# TAS5711.net
KiCad netlist of a schematic drawn in Altium Designer
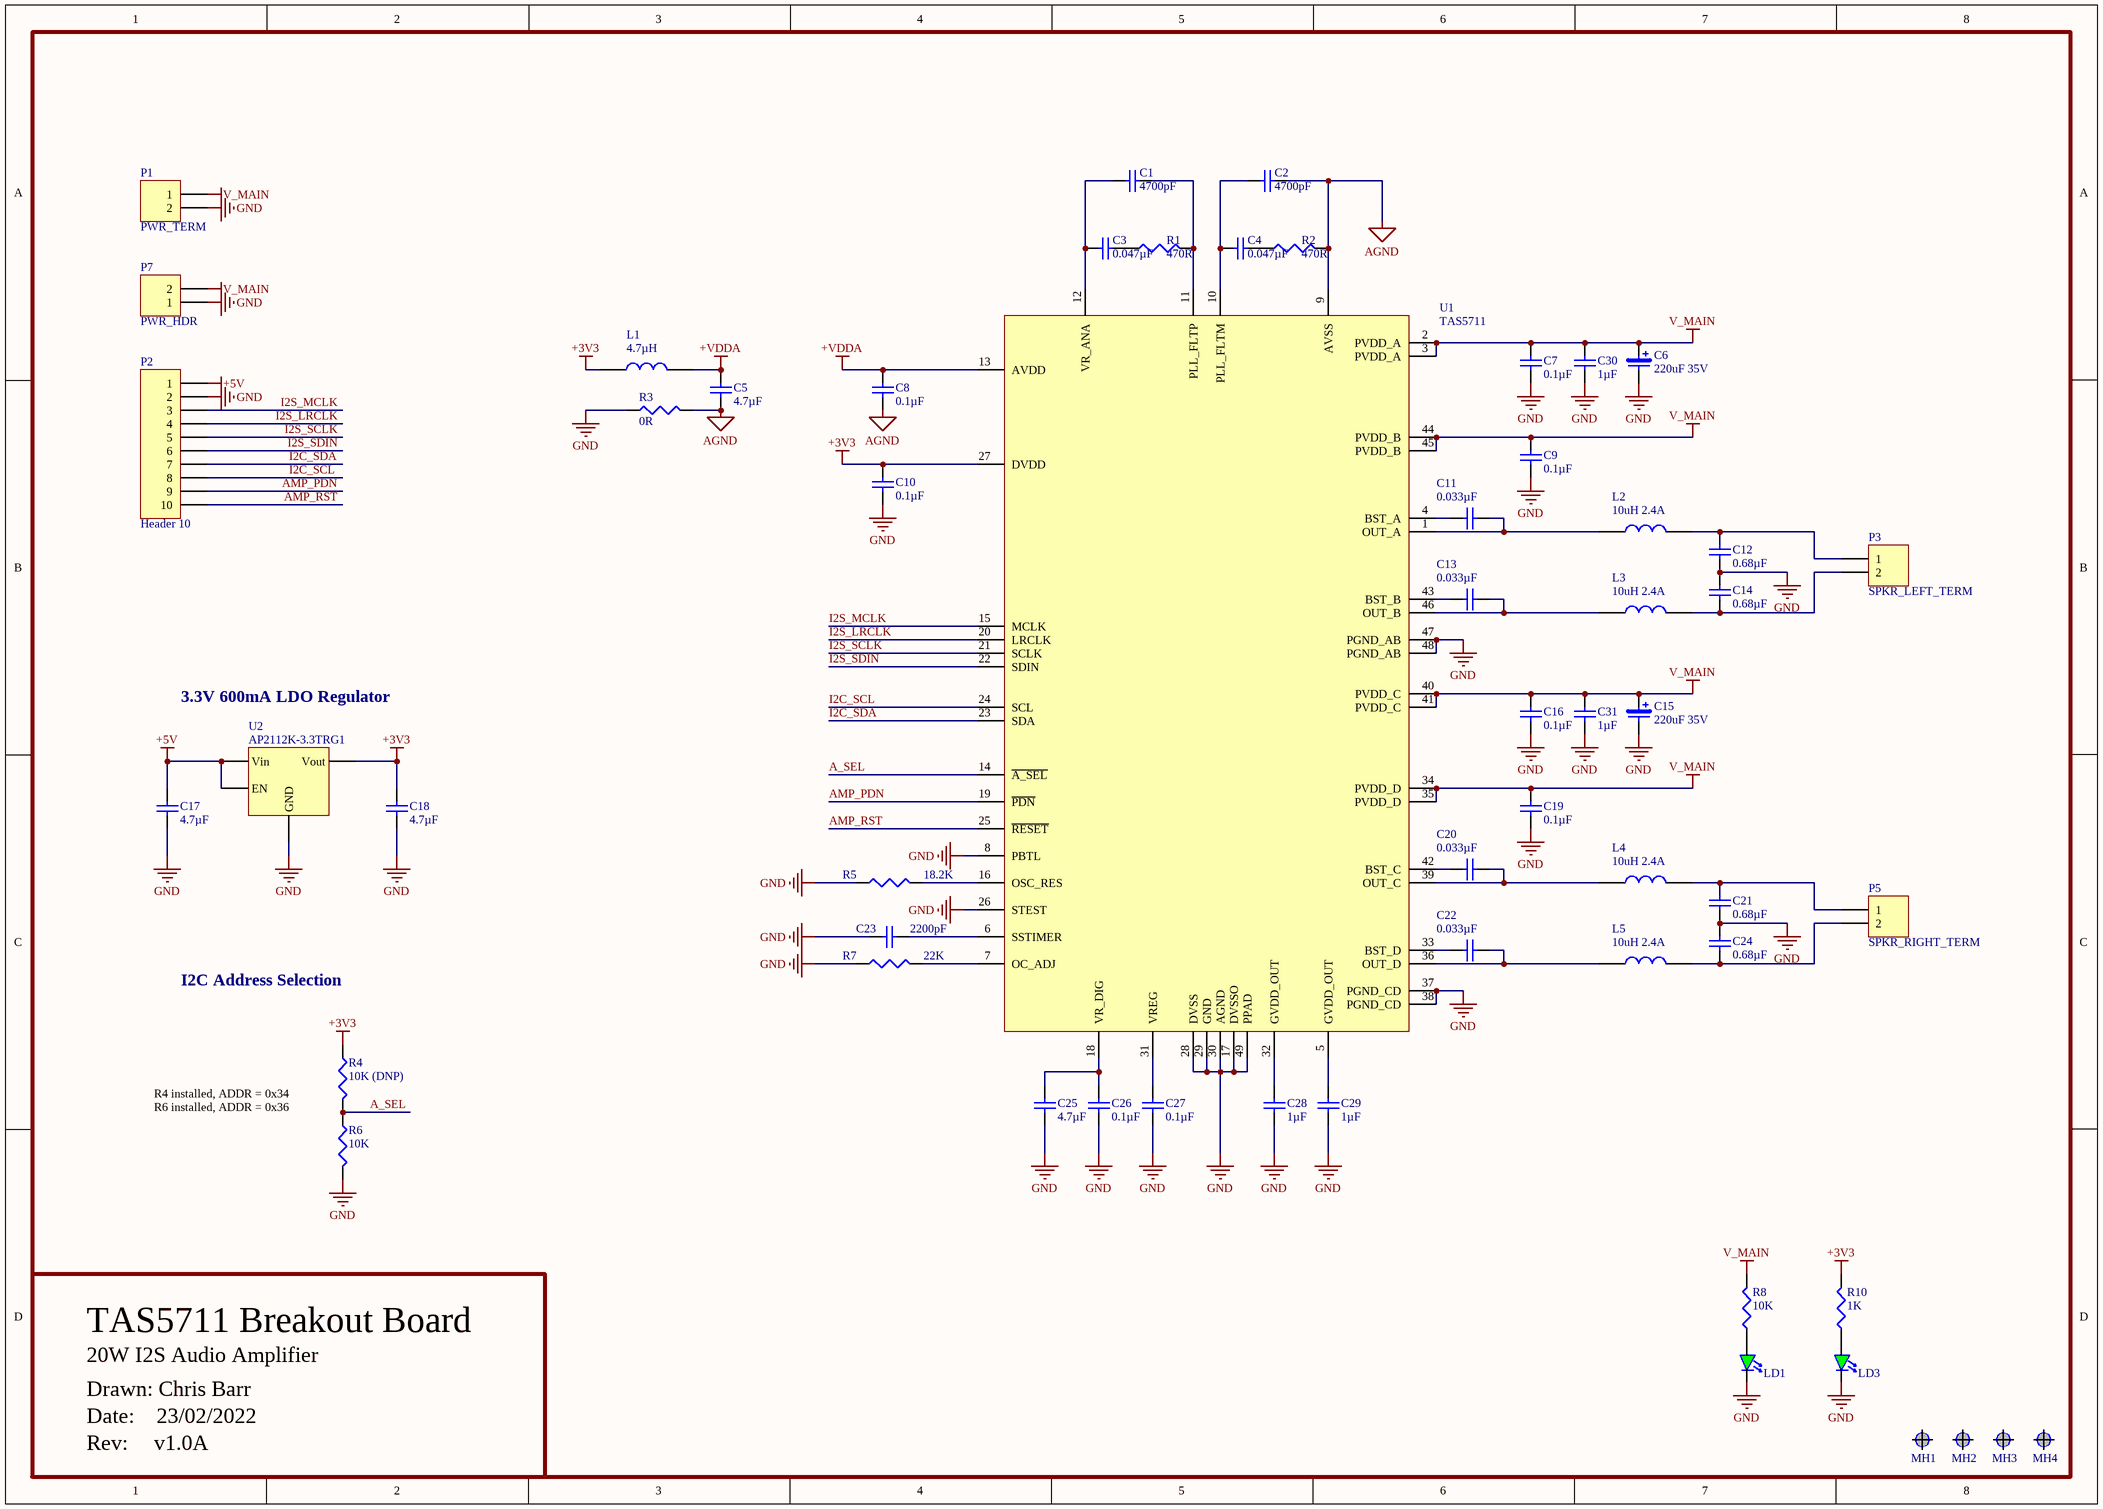
[diagram p0: TAS5711.SchDoc]

(export (version "E")
  (design (tool "Eeschema 10.0.6"))
  (components
    (comp (ref "C1")
      (value "4700pF")
      (footprint "CAPC1608X90N")
      (description "CAP CER 4700PF 50V X7R 0603")
      (fields (field (name "VOLTAGE") "50V") (field (name "TOLERANCE") "±10%"))
      (libsource (lib "Ceramic Cap DBLIB") (part "Capacitor"))
    )
    (comp (ref "C2")
      (value "4700pF")
      (footprint "CAPC1608X90N")
      (description "CAP CER 4700PF 50V X7R 0603")
      (fields (field (name "VOLTAGE") "50V") (field (name "TOLERANCE") "±10%"))
      (libsource (lib "Ceramic Cap DBLIB") (part "Capacitor"))
    )
    (comp (ref "C3")
      (value "0.047µF")
      (footprint "CAPC1608X90N")
      (description "CAP CER 0.047UF 25V X5R 0603")
      (fields (field (name "VOLTAGE") "25V") (field (name "TOLERANCE") "±10%"))
      (libsource (lib "Ceramic Cap DBLIB") (part "Capacitor"))
    )
    (comp (ref "C4")
      (value "0.047µF")
      (footprint "CAPC1608X90N")
      (description "CAP CER 0.047UF 25V X5R 0603")
      (fields (field (name "VOLTAGE") "25V") (field (name "TOLERANCE") "±10%"))
      (libsource (lib "Ceramic Cap DBLIB") (part "Capacitor"))
    )
    (comp (ref "C5")
      (value "4.7µF")
      (footprint "CAPC1608X90N")
      (description "CAP CER 4.7UF 16V X5R 0603")
      (fields (field (name "VOLTAGE") "16V") (field (name "TOLERANCE") "±10%"))
      (libsource (lib "Ceramic Cap DBLIB") (part "Capacitor"))
    )
    (comp (ref "C6")
      (value "220uF 35V")
      (footprint "CAPAE250P680X1220_VERT")
      (description "CAP ALUM 220UF 20% 35V RADIAL")
      (fields (field (name "Comment") "CapE-8.0-THT-220uF-35V") (field (name "PUBLISHER") "Altium Limited"))
      (libsource (lib "main_library") (part "CapE-8.0-THT-220uF-35V"))
    )
    (comp (ref "C7")
      (value "0.1µF")
      (footprint "CAPC1608X90N")
      (description "CAP CER 0.1UF 50V X7R 0603")
      (fields (field (name "VOLTAGE") "50V") (field (name "TOLERANCE") "±10%"))
      (libsource (lib "Ceramic Cap DBLIB") (part "Capacitor"))
    )
    (comp (ref "C8")
      (value "0.1µF")
      (footprint "CAPC1608X90N")
      (description "CAP CER 0.1UF 50V X7R 0603")
      (fields (field (name "VOLTAGE") "50V") (field (name "TOLERANCE") "±10%"))
      (libsource (lib "Ceramic Cap DBLIB") (part "Capacitor"))
    )
    (comp (ref "C9")
      (value "0.1µF")
      (footprint "CAPC1608X90N")
      (description "CAP CER 0.1UF 50V X7R 0603")
      (fields (field (name "VOLTAGE") "50V") (field (name "TOLERANCE") "±10%"))
      (libsource (lib "Ceramic Cap DBLIB") (part "Capacitor"))
    )
    (comp (ref "C10")
      (value "0.1µF")
      (footprint "CAPC1608X90N")
      (description "CAP CER 0.1UF 50V X7R 0603")
      (fields (field (name "VOLTAGE") "50V") (field (name "TOLERANCE") "±10%"))
      (libsource (lib "Ceramic Cap DBLIB") (part "Capacitor"))
    )
    (comp (ref "C11")
      (value "0.033µF")
      (footprint "CAPC1608X90N")
      (description "CAP CER 0.033UF 50V X7R 0603")
      (fields (field (name "VOLTAGE") "50V") (field (name "TOLERANCE") "±10%"))
      (libsource (lib "Ceramic Cap DBLIB") (part "Capacitor"))
    )
    (comp (ref "C12")
      (value "0.68µF")
      (footprint "CAPC3216X100N")
      (description "CAP CER 0.68UF 100V X7R 1206")
      (fields (field (name "VOLTAGE") "100V") (field (name "TOLERANCE") "±10%"))
      (libsource (lib "Ceramic Cap DBLIB") (part "Capacitor"))
    )
    (comp (ref "C13")
      (value "0.033µF")
      (footprint "CAPC1608X90N")
      (description "CAP CER 0.033UF 50V X7R 0603")
      (fields (field (name "VOLTAGE") "50V") (field (name "TOLERANCE") "±10%"))
      (libsource (lib "Ceramic Cap DBLIB") (part "Capacitor"))
    )
    (comp (ref "C14")
      (value "0.68µF")
      (footprint "CAPC3216X100N")
      (description "CAP CER 0.68UF 100V X7R 1206")
      (fields (field (name "VOLTAGE") "100V") (field (name "TOLERANCE") "±10%"))
      (libsource (lib "Ceramic Cap DBLIB") (part "Capacitor"))
    )
    (comp (ref "C15")
      (value "220uF 35V")
      (footprint "CAPAE250P680X1220_VERT")
      (description "CAP ALUM 220UF 20% 35V RADIAL")
      (fields (field (name "Comment") "CapE-8.0-THT-220uF-35V") (field (name "PUBLISHER") "Altium Limited"))
      (libsource (lib "main_library") (part "CapE-8.0-THT-220uF-35V"))
    )
    (comp (ref "C16")
      (value "0.1µF")
      (footprint "CAPC1608X90N")
      (description "CAP CER 0.1UF 50V X7R 0603")
      (fields (field (name "VOLTAGE") "50V") (field (name "TOLERANCE") "±10%"))
      (libsource (lib "Ceramic Cap DBLIB") (part "Capacitor"))
    )
    (comp (ref "C17")
      (value "4.7µF")
      (footprint "CAPC1608X90N")
      (description "CAP CER 4.7UF 16V X5R 0603")
      (fields (field (name "VOLTAGE") "16V") (field (name "TOLERANCE") "±10%"))
      (libsource (lib "Ceramic Cap DBLIB") (part "Capacitor"))
    )
    (comp (ref "C18")
      (value "4.7µF")
      (footprint "CAPC1608X90N")
      (description "CAP CER 4.7UF 16V X5R 0603")
      (fields (field (name "VOLTAGE") "16V") (field (name "TOLERANCE") "±10%"))
      (libsource (lib "Ceramic Cap DBLIB") (part "Capacitor"))
    )
    (comp (ref "C19")
      (value "0.1µF")
      (footprint "CAPC1608X90N")
      (description "CAP CER 0.1UF 50V X7R 0603")
      (fields (field (name "VOLTAGE") "50V") (field (name "TOLERANCE") "±10%"))
      (libsource (lib "Ceramic Cap DBLIB") (part "Capacitor"))
    )
    (comp (ref "C20")
      (value "0.033µF")
      (footprint "CAPC1608X90N")
      (description "CAP CER 0.033UF 50V X7R 0603")
      (fields (field (name "VOLTAGE") "50V") (field (name "TOLERANCE") "±10%"))
      (libsource (lib "Ceramic Cap DBLIB") (part "Capacitor"))
    )
    (comp (ref "C21")
      (value "0.68µF")
      (footprint "CAPC3216X100N")
      (description "CAP CER 0.68UF 100V X7R 1206")
      (fields (field (name "VOLTAGE") "100V") (field (name "TOLERANCE") "±10%"))
      (libsource (lib "Ceramic Cap DBLIB") (part "Capacitor"))
    )
    (comp (ref "C22")
      (value "0.033µF")
      (footprint "CAPC1608X90N")
      (description "CAP CER 0.033UF 50V X7R 0603")
      (fields (field (name "VOLTAGE") "50V") (field (name "TOLERANCE") "±10%"))
      (libsource (lib "Ceramic Cap DBLIB") (part "Capacitor"))
    )
    (comp (ref "C23")
      (value "2200pF")
      (footprint "CAPC1608X90N")
      (description "CAP CER 2200PF 100V X5R 0603")
      (fields (field (name "VOLTAGE") "100V") (field (name "TOLERANCE") "±20%"))
      (libsource (lib "Ceramic Cap DBLIB") (part "Capacitor"))
    )
    (comp (ref "C24")
      (value "0.68µF")
      (footprint "CAPC3216X100N")
      (description "CAP CER 0.68UF 100V X7R 1206")
      (fields (field (name "VOLTAGE") "100V") (field (name "TOLERANCE") "±10%"))
      (libsource (lib "Ceramic Cap DBLIB") (part "Capacitor"))
    )
    (comp (ref "C25")
      (value "4.7µF")
      (footprint "CAPC1608X90N")
      (description "CAP CER 4.7UF 16V X5R 0603")
      (fields (field (name "VOLTAGE") "16V") (field (name "TOLERANCE") "±10%"))
      (libsource (lib "Ceramic Cap DBLIB") (part "Capacitor"))
    )
    (comp (ref "C26")
      (value "0.1µF")
      (footprint "CAPC1608X90N")
      (description "CAP CER 0.1UF 50V X7R 0603")
      (fields (field (name "VOLTAGE") "50V") (field (name "TOLERANCE") "±10%"))
      (libsource (lib "Ceramic Cap DBLIB") (part "Capacitor"))
    )
    (comp (ref "C27")
      (value "0.1µF")
      (footprint "CAPC1608X90N")
      (description "CAP CER 0.1UF 50V X7R 0603")
      (fields (field (name "VOLTAGE") "50V") (field (name "TOLERANCE") "±10%"))
      (libsource (lib "Ceramic Cap DBLIB") (part "Capacitor"))
    )
    (comp (ref "C28")
      (value "1µF")
      (footprint "CAPC1608X90N")
      (description "CAP CER 1UF 35V X5R 0603")
      (fields (field (name "VOLTAGE") "35V") (field (name "TOLERANCE") "±10%"))
      (libsource (lib "Ceramic Cap DBLIB") (part "Capacitor"))
    )
    (comp (ref "C29")
      (value "1µF")
      (footprint "CAPC1608X90N")
      (description "CAP CER 1UF 35V X5R 0603")
      (fields (field (name "VOLTAGE") "35V") (field (name "TOLERANCE") "±10%"))
      (libsource (lib "Ceramic Cap DBLIB") (part "Capacitor"))
    )
    (comp (ref "C30")
      (value "1µF")
      (footprint "CAPC1608X90N")
      (description "CAP CER 1UF 35V X5R 0603")
      (fields (field (name "VOLTAGE") "35V") (field (name "TOLERANCE") "±10%"))
      (libsource (lib "Ceramic Cap DBLIB") (part "Capacitor"))
    )
    (comp (ref "C31")
      (value "1µF")
      (footprint "CAPC1608X90N")
      (description "CAP CER 1UF 35V X5R 0603")
      (fields (field (name "VOLTAGE") "35V") (field (name "TOLERANCE") "±10%"))
      (libsource (lib "Ceramic Cap DBLIB") (part "Capacitor"))
    )
    (comp (ref "L1")
      (value "4.7µH")
      (footprint "Res 2012-0805")
      (description "FIXED IND 4.7UH 500MA 300MOHM SM")
      (fields (field (name "PUBLISHER") "Altium Limited"))
      (libsource (lib "main_library") (part "Ferrite Bead SMD 0805"))
    )
    (comp (ref "L2")
      (value "10uH 2.4A")
      (footprint "SRN6045TA SMD Inductor")
      (description "FIXED IND 10UH 2.4A 59.8MOHM SMD")
      (fields (field (name "Comment") "Inductor SMD 10uH 2.4A") (field (name "PUBLISHER") "Altium Limited"))
      (libsource (lib "main_library") (part "Inductor SMD 33uH 2.5A"))
    )
    (comp (ref "L3")
      (value "10uH 2.4A")
      (footprint "SRN6045TA SMD Inductor")
      (description "FIXED IND 10UH 2.4A 59.8MOHM SMD")
      (fields (field (name "Comment") "Inductor SMD 10uH 2.4A") (field (name "PUBLISHER") "Altium Limited"))
      (libsource (lib "main_library") (part "Inductor SMD 33uH 2.5A"))
    )
    (comp (ref "L4")
      (value "10uH 2.4A")
      (footprint "SRN6045TA SMD Inductor")
      (description "FIXED IND 10UH 2.4A 59.8MOHM SMD")
      (fields (field (name "Comment") "Inductor SMD 10uH 2.4A") (field (name "PUBLISHER") "Altium Limited"))
      (libsource (lib "main_library") (part "Inductor SMD 33uH 2.5A"))
    )
    (comp (ref "L5")
      (value "10uH 2.4A")
      (footprint "SRN6045TA SMD Inductor")
      (description "FIXED IND 10UH 2.4A 59.8MOHM SMD")
      (fields (field (name "Comment") "Inductor SMD 10uH 2.4A") (field (name "PUBLISHER") "Altium Limited"))
      (libsource (lib "main_library") (part "Inductor SMD 33uH 2.5A"))
    )
    (comp (ref "LD1")
      (value "LEDG  0603")
      (footprint "LED 1608-0603")
      (description "LED GREEN CLEAR CHIP SMD 0603")
      (libsource (lib "main_library") (part "LEDG  0603"))
    )
    (comp (ref "LD3")
      (value "LEDG  0603")
      (footprint "LED 1608-0603")
      (description "LED GREEN CLEAR CHIP SMD 0603")
      (libsource (lib "main_library") (part "LEDG  0603"))
    )
    (comp (ref "MH1")
      (value "Screw Hole")
      (footprint "M3-Hole-2")
      (libsource (lib "main_library") (part "Screw Hole"))
    )
    (comp (ref "MH2")
      (value "Screw Hole")
      (footprint "M3-Hole-2")
      (libsource (lib "main_library") (part "Screw Hole"))
    )
    (comp (ref "MH3")
      (value "Screw Hole")
      (footprint "M3-Hole-2")
      (libsource (lib "main_library") (part "Screw Hole"))
    )
    (comp (ref "MH4")
      (value "Screw Hole")
      (footprint "M3-Hole-2")
      (libsource (lib "main_library") (part "Screw Hole"))
    )
    (comp (ref "P1")
      (value "PWR_TERM")
      (footprint "TERM2 3.5mm")
      (description "Screw Terminal 3.5mm 2-Way")
      (libsource (lib "main_library") (part "ScrewTerminal-3.5mm-2Way"))
    )
    (comp (ref "P2")
      (value "Header 10")
      (footprint "HDR1X10")
      (description "Header, 10-Pin")
      (fields (field (name "PUBLISHER") "Altium Limited"))
      (libsource (lib "Miscellaneous Connectors") (part "Header 10"))
    )
    (comp (ref "P3")
      (value "SPKR_LEFT_TERM")
      (footprint "TERM2 3.5mm")
      (description "Screw Terminal 3.5mm 2-Way")
      (libsource (lib "") (part "ScrewTerminal-3.5mm-2Way_1"))
    )
    (comp (ref "P5")
      (value "SPKR_RIGHT_TERM")
      (footprint "TERM2 3.5mm")
      (description "Screw Terminal 3.5mm 2-Way")
      (libsource (lib "") (part "ScrewTerminal-3.5mm-2Way_1"))
    )
    (comp (ref "P7")
      (value "PWR_HDR")
      (footprint "HDR1X2-HEADER")
      (description "Header, 2-Pin")
      (libsource (lib "main_library") (part "Header 1X2"))
    )
    (comp (ref "R1")
      (value "470R")
      (footprint "RES 1608-0603")
      (description "RES SMD 470 OHM 1% 1/10W 0603")
      (fields
        (field (name "TOLERANCE") "±1%")
        (field (name "Comment") "Resistor")
        (field (name "PUBLISHER") "Altium Limited")
      )
      (libsource (lib "Database_Libs1") (part "Resistor"))
    )
    (comp (ref "R2")
      (value "470R")
      (footprint "RES 1608-0603")
      (description "RES SMD 470 OHM 1% 1/10W 0603")
      (fields
        (field (name "TOLERANCE") "±1%")
        (field (name "Comment") "Resistor")
        (field (name "PUBLISHER") "Altium Limited")
      )
      (libsource (lib "Database_Libs1") (part "Resistor"))
    )
    (comp (ref "R3")
      (value "0R")
      (footprint "RES 1608-0603")
      (description "RES 0 OHM JUMPER 1/10W 0603")
      (fields (field (name "Comment") "Res-0603-0R") (field (name "PUBLISHER") "Altium Limited"))
      (libsource (lib "main_library") (part "Res-0603-0R"))
    )
    (comp (ref "R4")
      (value "10K (DNP)")
      (footprint "RES 1608-0603")
      (description "RES SMD 10K OHM 1% 1/10W 0603")
      (fields
        (field (name "TOLERANCE") "±1%")
        (field (name "Comment") "Resistor")
        (field (name "PUBLISHER") "Altium Limited")
      )
      (libsource (lib "Database_Libs1") (part "Resistor"))
    )
    (comp (ref "R5")
      (value "18.2K")
      (footprint "RES 1608-0603")
      (description "RES SMD 18.2K OHM 1% 1/10W 0603")
      (fields
        (field (name "TOLERANCE") "±1%")
        (field (name "Comment") "Resistor")
        (field (name "PUBLISHER") "Altium Limited")
      )
      (libsource (lib "Database_Libs1") (part "Resistor"))
    )
    (comp (ref "R6")
      (value "10K")
      (footprint "RES 1608-0603")
      (description "RES SMD 10K OHM 1% 1/10W 0603")
      (fields
        (field (name "TOLERANCE") "±1%")
        (field (name "Comment") "Resistor")
        (field (name "PUBLISHER") "Altium Limited")
      )
      (libsource (lib "Database_Libs1") (part "Resistor"))
    )
    (comp (ref "R7")
      (value "22K")
      (footprint "RES 1608-0603")
      (description "RES SMD 22K OHM 1% 1/10W 0603")
      (fields
        (field (name "TOLERANCE") "±1%")
        (field (name "Comment") "Resistor")
        (field (name "PUBLISHER") "Altium Limited")
      )
      (libsource (lib "Database_Libs1") (part "Resistor"))
    )
    (comp (ref "R8")
      (value "10K")
      (footprint "RES 1608-0603")
      (description "RES SMD 10K OHM 1% 1/10W 0603")
      (fields
        (field (name "TOLERANCE") "±1%")
        (field (name "Comment") "Resistor")
        (field (name "PUBLISHER") "Altium Limited")
      )
      (libsource (lib "Database_Libs1") (part "Resistor"))
    )
    (comp (ref "R10")
      (value "1K")
      (footprint "RES 1608-0603")
      (description "RES SMD 1K OHM 1% 1/10W 0603")
      (fields
        (field (name "TOLERANCE") "±1%")
        (field (name "Comment") "Resistor")
        (field (name "PUBLISHER") "Altium Limited")
      )
      (libsource (lib "Database_Libs1") (part "Resistor"))
    )
    (comp (ref "U1")
      (value "TAS5711")
      (footprint "TSQFP50P900X900X105_HS-49M")
      (description "IC AMP D DUAL/QUAD 21W 48HTQFP")
      (libsource (lib "main_library") (part "IC - DAC, I2S Amplifier - TAS5711"))
    )
    (comp (ref "U2")
      (value "AP2112K-3.3TRG1")
      (footprint "SOT23-5")
      (description "IC REG LINEAR 3.3V 600MA SOT25")
      (libsource (lib "picoprint_library") (part "Regulator - AP2112K 3.3V Linear Regulator"))
    )
  )
  (nets
    (net (code "1") (name "+3V3") (class "Default")
      (node (ref "C10") (pin "2") (pinfunction "2_2") (pintype "passive"))
      (node (ref "C18") (pin "2") (pinfunction "2_2") (pintype "passive"))
      (node (ref "L1") (pin "1") (pinfunction "1_1") (pintype "passive"))
      (node (ref "R10") (pin "2") (pinfunction "2_2") (pintype "passive"))
      (node (ref "R4") (pin "1") (pinfunction "1_1") (pintype "passive"))
      (node (ref "U1") (pin "27") (pinfunction "DVDD_27") (pintype "passive"))
      (node (ref "U2") (pin "5") (pinfunction "Vout_5") (pintype "passive"))
    )
    (net (code "2") (name "+5V") (class "Default")
      (node (ref "C17") (pin "2") (pinfunction "2_2") (pintype "passive"))
      (node (ref "P2") (pin "1") (pinfunction "1_1") (pintype "passive"))
      (node (ref "U2") (pin "1") (pinfunction "Vin_1") (pintype "passive"))
      (node (ref "U2") (pin "3") (pinfunction "EN_3") (pintype "passive"))
    )
    (net (code "3") (name "+VDDA") (class "Default")
      (node (ref "C5") (pin "2") (pinfunction "2_2") (pintype "passive"))
      (node (ref "C8") (pin "2") (pinfunction "2_2") (pintype "passive"))
      (node (ref "L1") (pin "2") (pinfunction "2_2") (pintype "passive"))
      (node (ref "U1") (pin "13") (pinfunction "AVDD_13") (pintype "passive"))
    )
    (net (code "4") (name "/AMP_PDN") (class "Default")
      (node (ref "P2") (pin "9") (pinfunction "9_9") (pintype "passive"))
      (node (ref "U1") (pin "19") (pinfunction "~{PDN}_19") (pintype "passive"))
    )
    (net (code "5") (name "/AMP_RST") (class "Default")
      (node (ref "P2") (pin "10") (pinfunction "10_10") (pintype "passive"))
      (node (ref "U1") (pin "25") (pinfunction "~{RESET}_25") (pintype "passive"))
    )
    (net (code "6") (name "/A_SEL") (class "Default")
      (node (ref "R4") (pin "2") (pinfunction "2_2") (pintype "passive"))
      (node (ref "R6") (pin "1") (pinfunction "1_1") (pintype "passive"))
      (node (ref "U1") (pin "14") (pinfunction "~{A_SEL}_14") (pintype "passive"))
    )
    (net (code "7") (name "/I2C_SCL") (class "Default")
      (node (ref "P2") (pin "8") (pinfunction "8_8") (pintype "passive"))
      (node (ref "U1") (pin "24") (pinfunction "SCL_24") (pintype "passive"))
    )
    (net (code "8") (name "/I2C_SDA") (class "Default")
      (node (ref "P2") (pin "7") (pinfunction "7_7") (pintype "passive"))
      (node (ref "U1") (pin "23") (pinfunction "SDA_23") (pintype "passive"))
    )
    (net (code "9") (name "/I2S_LRCLK") (class "Default")
      (node (ref "P2") (pin "4") (pinfunction "4_4") (pintype "passive"))
      (node (ref "U1") (pin "20") (pinfunction "LRCLK_20") (pintype "passive"))
    )
    (net (code "10") (name "/I2S_MCLK") (class "Default")
      (node (ref "P2") (pin "3") (pinfunction "3_3") (pintype "passive"))
      (node (ref "U1") (pin "15") (pinfunction "MCLK_15") (pintype "passive"))
    )
    (net (code "11") (name "/I2S_SCLK") (class "Default")
      (node (ref "P2") (pin "5") (pinfunction "5_5") (pintype "passive"))
      (node (ref "U1") (pin "21") (pinfunction "SCLK_21") (pintype "passive"))
    )
    (net (code "12") (name "/I2S_SDIN") (class "Default")
      (node (ref "P2") (pin "6") (pinfunction "6_6") (pintype "passive"))
      (node (ref "U1") (pin "22") (pinfunction "SDIN_22") (pintype "passive"))
    )
    (net (code "13") (name "AGND") (class "Default")
      (node (ref "C2") (pin "2") (pinfunction "2_2") (pintype "passive"))
      (node (ref "C5") (pin "1") (pinfunction "1_1") (pintype "passive"))
      (node (ref "C8") (pin "1") (pinfunction "1_1") (pintype "passive"))
      (node (ref "R2") (pin "2") (pinfunction "2_2") (pintype "passive"))
      (node (ref "R3") (pin "2") (pinfunction "2_2") (pintype "passive"))
      (node (ref "U1") (pin "9") (pinfunction "AVSS_9") (pintype "passive"))
    )
    (net (code "14") (name "GND") (class "Default")
      (node (ref "C10") (pin "1") (pinfunction "1_1") (pintype "passive"))
      (node (ref "C12") (pin "1") (pinfunction "1_1") (pintype "passive"))
      (node (ref "C14") (pin "2") (pinfunction "2_2") (pintype "passive"))
      (node (ref "C15") (pin "2") (pinfunction "2_2") (pintype "passive"))
      (node (ref "C16") (pin "1") (pinfunction "1_1") (pintype "passive"))
      (node (ref "C17") (pin "1") (pinfunction "1_1") (pintype "passive"))
      (node (ref "C18") (pin "1") (pinfunction "1_1") (pintype "passive"))
      (node (ref "C19") (pin "1") (pinfunction "1_1") (pintype "passive"))
      (node (ref "C21") (pin "1") (pinfunction "1_1") (pintype "passive"))
      (node (ref "C23") (pin "1") (pinfunction "1_1") (pintype "passive"))
      (node (ref "C24") (pin "2") (pinfunction "2_2") (pintype "passive"))
      (node (ref "C25") (pin "1") (pinfunction "1_1") (pintype "passive"))
      (node (ref "C26") (pin "1") (pinfunction "1_1") (pintype "passive"))
      (node (ref "C27") (pin "1") (pinfunction "1_1") (pintype "passive"))
      (node (ref "C28") (pin "1") (pinfunction "1_1") (pintype "passive"))
      (node (ref "C29") (pin "1") (pinfunction "1_1") (pintype "passive"))
      (node (ref "C30") (pin "1") (pinfunction "1_1") (pintype "passive"))
      (node (ref "C31") (pin "1") (pinfunction "1_1") (pintype "passive"))
      (node (ref "C6") (pin "2") (pinfunction "2_2") (pintype "passive"))
      (node (ref "C7") (pin "1") (pinfunction "1_1") (pintype "passive"))
      (node (ref "C9") (pin "1") (pinfunction "1_1") (pintype "passive"))
      (node (ref "LD1") (pin "2") (pinfunction "K_2") (pintype "passive"))
      (node (ref "LD3") (pin "2") (pinfunction "K_2") (pintype "passive"))
      (node (ref "P1") (pin "2") (pinfunction "2_2") (pintype "power_in"))
      (node (ref "P2") (pin "2") (pinfunction "2_2") (pintype "passive"))
      (node (ref "P7") (pin "1") (pinfunction "1_1") (pintype "passive"))
      (node (ref "R3") (pin "1") (pinfunction "1_1") (pintype "passive"))
      (node (ref "R5") (pin "1") (pinfunction "1_1") (pintype "passive"))
      (node (ref "R6") (pin "2") (pinfunction "2_2") (pintype "passive"))
      (node (ref "R7") (pin "1") (pinfunction "1_1") (pintype "passive"))
      (node (ref "U1") (pin "17") (pinfunction "DVSSO_17") (pintype "passive"))
      (node (ref "U1") (pin "26") (pinfunction "STEST_26") (pintype "passive"))
      (node (ref "U1") (pin "28") (pinfunction "DVSS_28") (pintype "passive"))
      (node (ref "U1") (pin "29") (pinfunction "GND_29") (pintype "passive"))
      (node (ref "U1") (pin "30") (pinfunction "AGND_30") (pintype "passive"))
      (node (ref "U1") (pin "37") (pinfunction "PGND_CD_37") (pintype "passive"))
      (node (ref "U1") (pin "38") (pinfunction "PGND_CD_38") (pintype "passive"))
      (node (ref "U1") (pin "47") (pinfunction "PGND_AB_47") (pintype "passive"))
      (node (ref "U1") (pin "48") (pinfunction "PGND_AB_48") (pintype "passive"))
      (node (ref "U1") (pin "49") (pinfunction "PPAD_49") (pintype "passive"))
      (node (ref "U1") (pin "8") (pinfunction "PBTL_8") (pintype "passive"))
      (node (ref "U2") (pin "2") (pinfunction "GND_2") (pintype "passive"))
    )
    (net (code "15") (name "Net-(C3-Pad2)") (class "Default")
      (node (ref "C3") (pin "2") (pinfunction "2_2") (pintype "passive"))
      (node (ref "R1") (pin "1") (pinfunction "1_1") (pintype "passive"))
    )
    (net (code "16") (name "Net-(C4-Pad2)") (class "Default")
      (node (ref "C4") (pin "2") (pinfunction "2_2") (pintype "passive"))
      (node (ref "R2") (pin "1") (pinfunction "1_1") (pintype "passive"))
    )
    (net (code "17") (name "Net-(C12-Pad2)") (class "Default")
      (node (ref "C12") (pin "2") (pinfunction "2_2") (pintype "passive"))
      (node (ref "L2") (pin "2") (pinfunction "2_2") (pintype "passive"))
      (node (ref "P3") (pin "1") (pinfunction "1_1") (pintype "power_in"))
    )
    (net (code "18") (name "Net-(C14-Pad1)") (class "Default")
      (node (ref "C14") (pin "1") (pinfunction "1_1") (pintype "passive"))
      (node (ref "L3") (pin "2") (pinfunction "2_2") (pintype "passive"))
      (node (ref "P3") (pin "2") (pinfunction "2_2") (pintype "power_in"))
    )
    (net (code "19") (name "Net-(C21-Pad2)") (class "Default")
      (node (ref "C21") (pin "2") (pinfunction "2_2") (pintype "passive"))
      (node (ref "L4") (pin "2") (pinfunction "2_2") (pintype "passive"))
      (node (ref "P5") (pin "1") (pinfunction "1_1") (pintype "power_in"))
    )
    (net (code "20") (name "Net-(C24-Pad1)") (class "Default")
      (node (ref "C24") (pin "1") (pinfunction "1_1") (pintype "passive"))
      (node (ref "L5") (pin "2") (pinfunction "2_2") (pintype "passive"))
      (node (ref "P5") (pin "2") (pinfunction "2_2") (pintype "power_in"))
    )
    (net (code "21") (name "Net-(C28-Pad2)") (class "Default")
      (node (ref "C28") (pin "2") (pinfunction "2_2") (pintype "passive"))
      (node (ref "U1") (pin "32") (pinfunction "GVDD_OUT_32") (pintype "passive"))
    )
    (net (code "22") (name "Net-(C29-Pad2)") (class "Default")
      (node (ref "C29") (pin "2") (pinfunction "2_2") (pintype "passive"))
      (node (ref "U1") (pin "5") (pinfunction "GVDD_OUT_5") (pintype "passive"))
    )
    (net (code "23") (name "Net-(LD1-A)") (class "Default")
      (node (ref "LD1") (pin "1") (pinfunction "A_1") (pintype "passive"))
      (node (ref "R8") (pin "1") (pinfunction "1_1") (pintype "passive"))
    )
    (net (code "24") (name "Net-(LD3-A)") (class "Default")
      (node (ref "LD3") (pin "1") (pinfunction "A_1") (pintype "passive"))
      (node (ref "R10") (pin "1") (pinfunction "1_1") (pintype "passive"))
    )
    (net (code "25") (name "Net-(U1-BST_A)") (class "Default")
      (node (ref "C11") (pin "1") (pinfunction "1_1") (pintype "passive"))
      (node (ref "U1") (pin "4") (pinfunction "BST_A_4") (pintype "passive"))
    )
    (net (code "26") (name "Net-(U1-BST_B)") (class "Default")
      (node (ref "C13") (pin "1") (pinfunction "1_1") (pintype "passive"))
      (node (ref "U1") (pin "43") (pinfunction "BST_B_43") (pintype "passive"))
    )
    (net (code "27") (name "Net-(U1-BST_C)") (class "Default")
      (node (ref "C20") (pin "1") (pinfunction "1_1") (pintype "passive"))
      (node (ref "U1") (pin "42") (pinfunction "BST_C_42") (pintype "passive"))
    )
    (net (code "28") (name "Net-(U1-BST_D)") (class "Default")
      (node (ref "C22") (pin "1") (pinfunction "1_1") (pintype "passive"))
      (node (ref "U1") (pin "33") (pinfunction "BST_D_33") (pintype "passive"))
    )
    (net (code "29") (name "Net-(U1-OC_ADJ)") (class "Default")
      (node (ref "R7") (pin "2") (pinfunction "2_2") (pintype "passive"))
      (node (ref "U1") (pin "7") (pinfunction "OC_ADJ_7") (pintype "passive"))
    )
    (net (code "30") (name "Net-(U1-OSC_RES)") (class "Default")
      (node (ref "R5") (pin "2") (pinfunction "2_2") (pintype "passive"))
      (node (ref "U1") (pin "16") (pinfunction "OSC_RES_16") (pintype "passive"))
    )
    (net (code "31") (name "Net-(U1-OUT_A)") (class "Default")
      (node (ref "C11") (pin "2") (pinfunction "2_2") (pintype "passive"))
      (node (ref "L2") (pin "1") (pinfunction "1_1") (pintype "passive"))
      (node (ref "U1") (pin "1") (pinfunction "OUT_A_1") (pintype "passive"))
    )
    (net (code "32") (name "Net-(U1-OUT_B)") (class "Default")
      (node (ref "C13") (pin "2") (pinfunction "2_2") (pintype "passive"))
      (node (ref "L3") (pin "1") (pinfunction "1_1") (pintype "passive"))
      (node (ref "U1") (pin "46") (pinfunction "OUT_B_46") (pintype "passive"))
    )
    (net (code "33") (name "Net-(U1-OUT_C)") (class "Default")
      (node (ref "C20") (pin "2") (pinfunction "2_2") (pintype "passive"))
      (node (ref "L4") (pin "1") (pinfunction "1_1") (pintype "passive"))
      (node (ref "U1") (pin "39") (pinfunction "OUT_C_39") (pintype "passive"))
    )
    (net (code "34") (name "Net-(U1-OUT_D)") (class "Default")
      (node (ref "C22") (pin "2") (pinfunction "2_2") (pintype "passive"))
      (node (ref "L5") (pin "1") (pinfunction "1_1") (pintype "passive"))
      (node (ref "U1") (pin "36") (pinfunction "OUT_D_36") (pintype "passive"))
    )
    (net (code "35") (name "Net-(U1-PLL_FLTM)") (class "Default")
      (node (ref "C2") (pin "1") (pinfunction "1_1") (pintype "passive"))
      (node (ref "C4") (pin "1") (pinfunction "1_1") (pintype "passive"))
      (node (ref "U1") (pin "10") (pinfunction "PLL_FLTM_10") (pintype "passive"))
    )
    (net (code "36") (name "Net-(U1-PLL_FLTP)") (class "Default")
      (node (ref "C1") (pin "2") (pinfunction "2_2") (pintype "passive"))
      (node (ref "R1") (pin "2") (pinfunction "2_2") (pintype "passive"))
      (node (ref "U1") (pin "11") (pinfunction "PLL_FLTP_11") (pintype "passive"))
    )
    (net (code "37") (name "Net-(U1-SSTIMER)") (class "Default")
      (node (ref "C23") (pin "2") (pinfunction "2_2") (pintype "passive"))
      (node (ref "U1") (pin "6") (pinfunction "SSTIMER_6") (pintype "passive"))
    )
    (net (code "38") (name "Net-(U1-VREG)") (class "Default")
      (node (ref "C27") (pin "2") (pinfunction "2_2") (pintype "passive"))
      (node (ref "U1") (pin "31") (pinfunction "VREG_31") (pintype "passive"))
    )
    (net (code "39") (name "Net-(U1-VR_ANA)") (class "Default")
      (node (ref "C1") (pin "1") (pinfunction "1_1") (pintype "passive"))
      (node (ref "C3") (pin "1") (pinfunction "1_1") (pintype "passive"))
      (node (ref "U1") (pin "12") (pinfunction "VR_ANA_12") (pintype "passive"))
    )
    (net (code "40") (name "Net-(U1-VR_DIG)") (class "Default")
      (node (ref "C25") (pin "2") (pinfunction "2_2") (pintype "passive"))
      (node (ref "C26") (pin "2") (pinfunction "2_2") (pintype "passive"))
      (node (ref "U1") (pin "18") (pinfunction "VR_DIG_18") (pintype "passive"))
    )
    (net (code "41") (name "V_MAIN") (class "Default")
      (node (ref "C15") (pin "1") (pinfunction "1_1") (pintype "passive"))
      (node (ref "C16") (pin "2") (pinfunction "2_2") (pintype "passive"))
      (node (ref "C19") (pin "2") (pinfunction "2_2") (pintype "passive"))
      (node (ref "C30") (pin "2") (pinfunction "2_2") (pintype "passive"))
      (node (ref "C31") (pin "2") (pinfunction "2_2") (pintype "passive"))
      (node (ref "C6") (pin "1") (pinfunction "1_1") (pintype "passive"))
      (node (ref "C7") (pin "2") (pinfunction "2_2") (pintype "passive"))
      (node (ref "C9") (pin "2") (pinfunction "2_2") (pintype "passive"))
      (node (ref "P1") (pin "1") (pinfunction "1_1") (pintype "power_in"))
      (node (ref "P7") (pin "2") (pinfunction "2_2") (pintype "passive"))
      (node (ref "R8") (pin "2") (pinfunction "2_2") (pintype "passive"))
      (node (ref "U1") (pin "2") (pinfunction "PVDD_A_2") (pintype "passive"))
      (node (ref "U1") (pin "3") (pinfunction "PVDD_A_3") (pintype "passive"))
      (node (ref "U1") (pin "34") (pinfunction "PVDD_D_34") (pintype "passive"))
      (node (ref "U1") (pin "35") (pinfunction "PVDD_D_35") (pintype "passive"))
      (node (ref "U1") (pin "40") (pinfunction "PVDD_C_40") (pintype "passive"))
      (node (ref "U1") (pin "41") (pinfunction "PVDD_C_41") (pintype "passive"))
      (node (ref "U1") (pin "44") (pinfunction "PVDD_B_44") (pintype "passive"))
      (node (ref "U1") (pin "45") (pinfunction "PVDD_B_45") (pintype "passive"))
    )
    (net (code "42") (name "unconnected-(MH1-0-PadM3)") (class "Default")
      (node (ref "MH1") (pin "M3") (pinfunction "0_M3") (pintype "passive"))
    )
    (net (code "43") (name "unconnected-(MH2-0-PadM3)") (class "Default")
      (node (ref "MH2") (pin "M3") (pinfunction "0_M3") (pintype "passive"))
    )
    (net (code "44") (name "unconnected-(MH3-0-PadM3)") (class "Default")
      (node (ref "MH3") (pin "M3") (pinfunction "0_M3") (pintype "passive"))
    )
    (net (code "45") (name "unconnected-(MH4-0-PadM3)") (class "Default")
      (node (ref "MH4") (pin "M3") (pinfunction "0_M3") (pintype "passive"))
    )
  )
)
